# Transmitter_Schematic.net
KiCad netlist of a schematic drawn in EAGLE
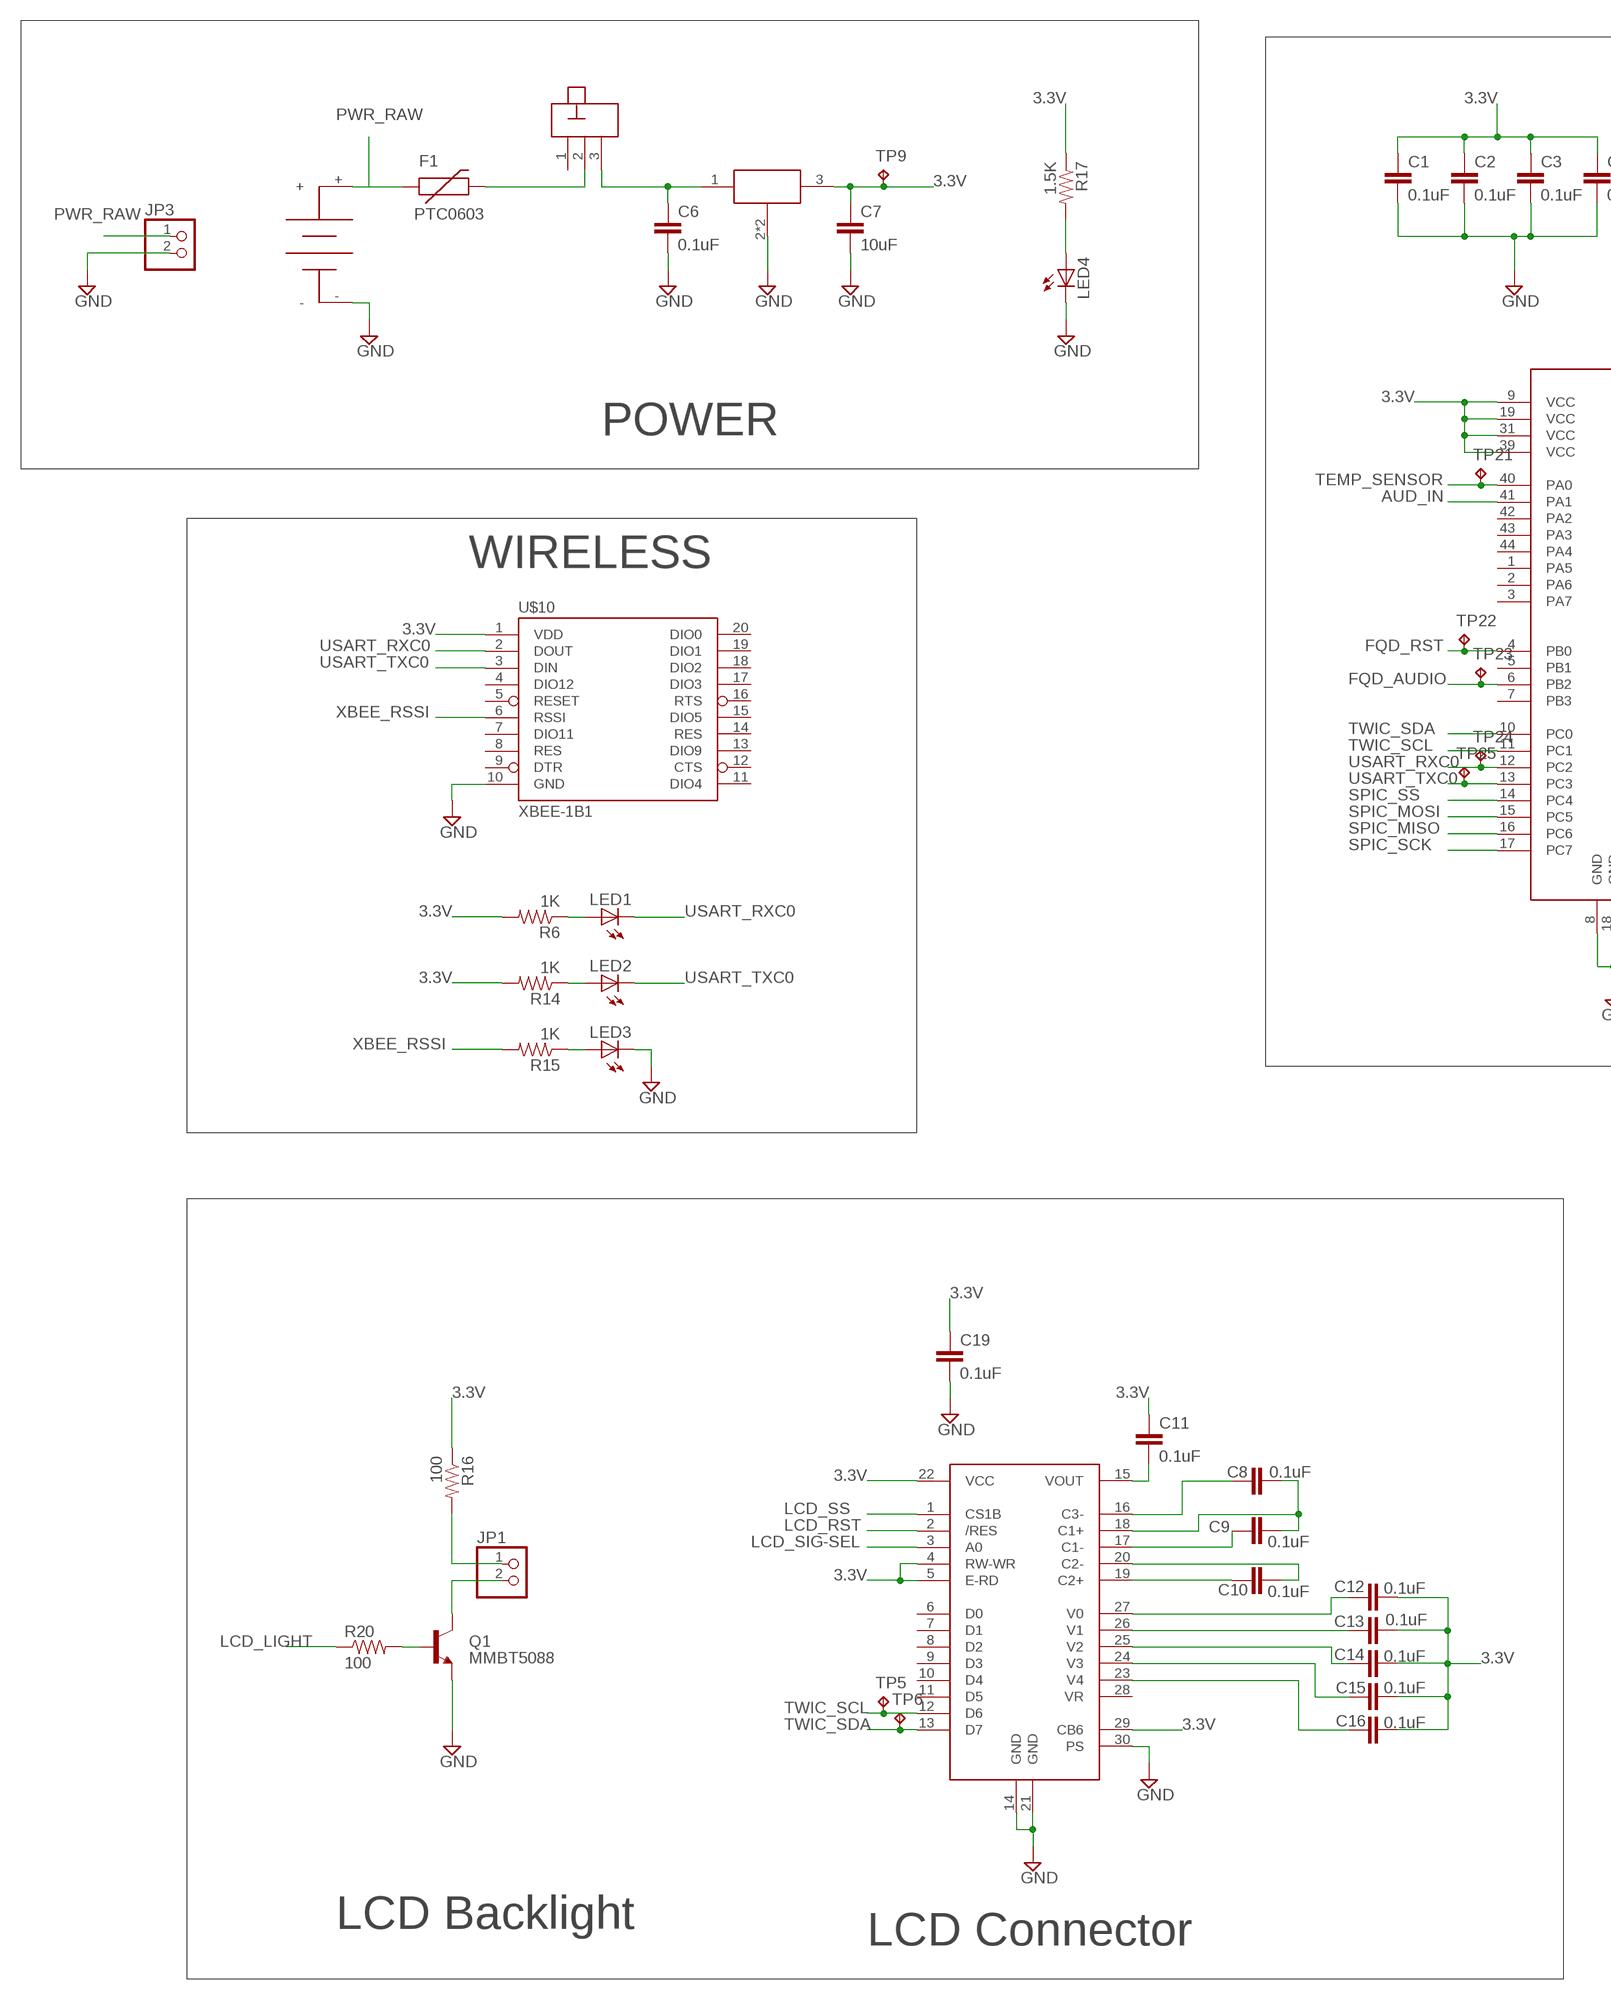
[diagram p0: schematic, sheet 1, part 1 of 2]
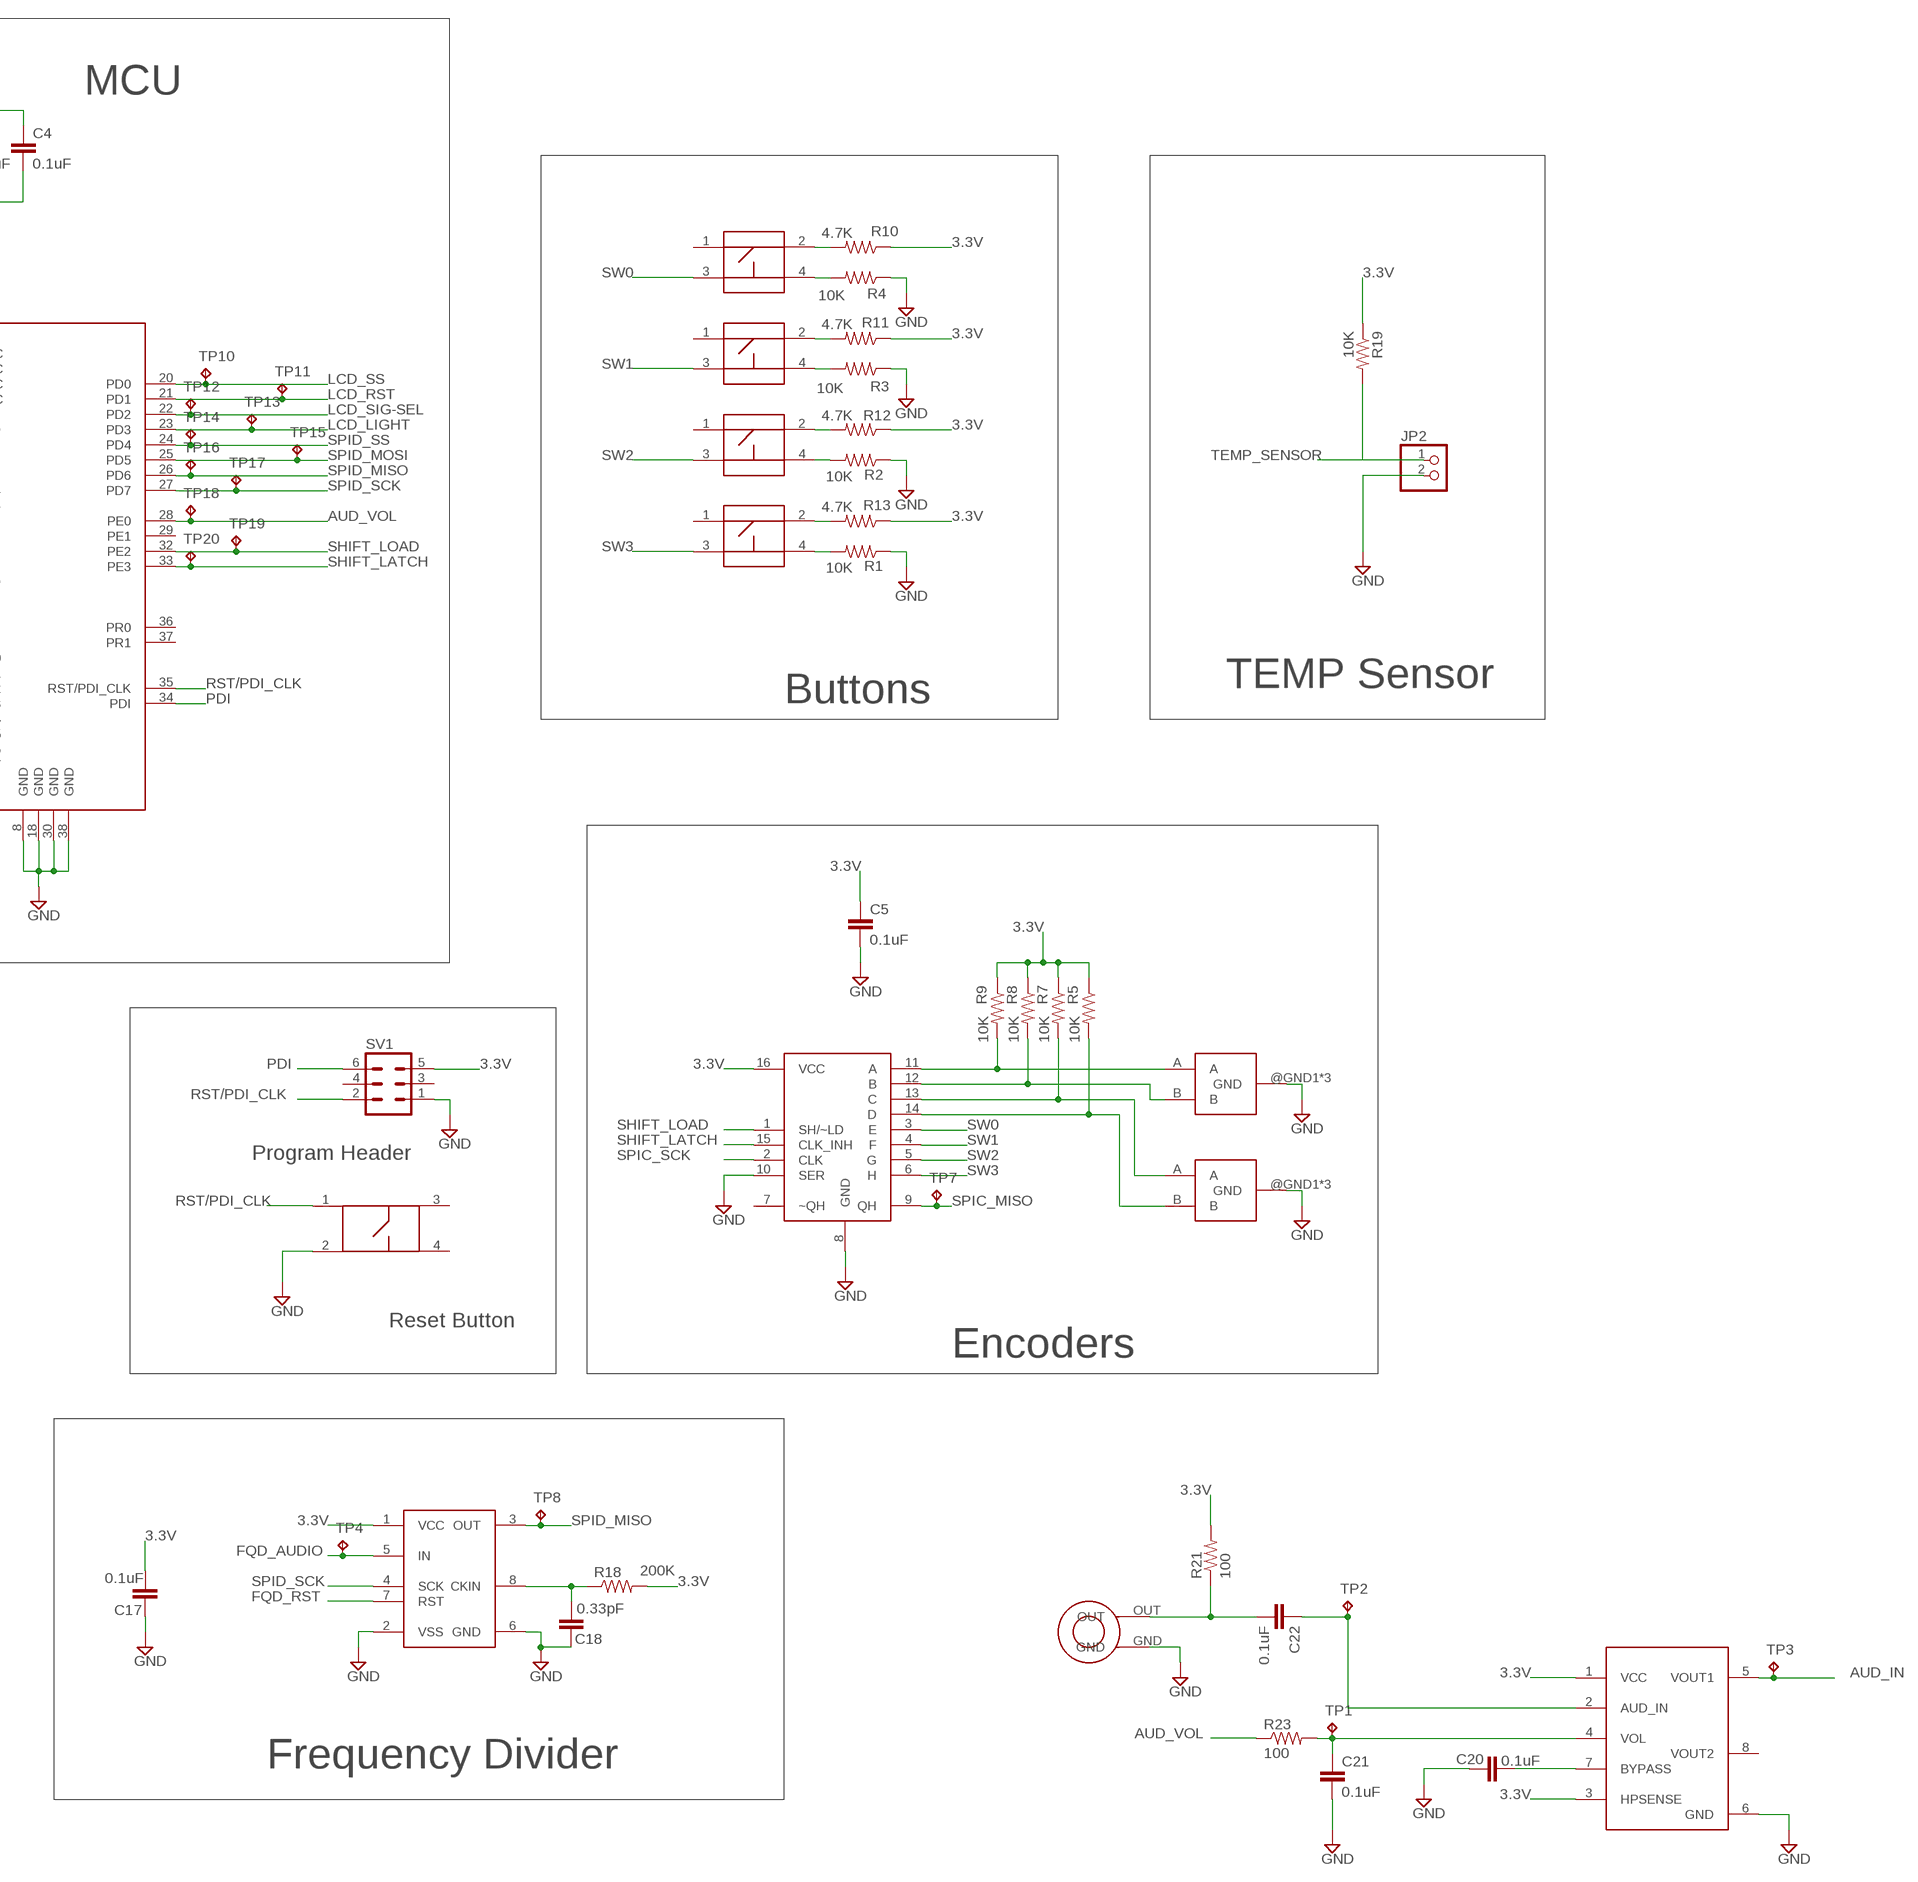
[diagram p1: schematic, sheet 1, part 2 of 2]

(export (version "E")
  (design (tool "Eeschema 10.0.6"))
  (components
    (comp (ref "C1")
      (value "0.1uF")
      (footprint "eagle-import:0603-CAP")
      (libsource (lib "eagle-import") (part "CAP0603-CAP"))
    )
    (comp (ref "C2")
      (value "0.1uF")
      (footprint "eagle-import:0603-CAP")
      (libsource (lib "eagle-import") (part "CAP0603-CAP"))
    )
    (comp (ref "C3")
      (value "0.1uF")
      (footprint "eagle-import:0603-CAP")
      (libsource (lib "eagle-import") (part "CAP0603-CAP"))
    )
    (comp (ref "C4")
      (value "0.1uF")
      (footprint "eagle-import:0603-CAP")
      (libsource (lib "eagle-import") (part "CAP0603-CAP"))
    )
    (comp (ref "C5")
      (value "0.1uF")
      (footprint "eagle-import:0603-CAP")
      (libsource (lib "eagle-import") (part "CAP0603-CAP"))
    )
    (comp (ref "C6")
      (value "0.1uF")
      (footprint "eagle-import:0603-CAP")
      (libsource (lib "eagle-import") (part "CAP0603-CAP"))
    )
    (comp (ref "C7")
      (value "10uF")
      (footprint "eagle-import:0603-CAP")
      (libsource (lib "eagle-import") (part "CAP0603-CAP"))
    )
    (comp (ref "C8")
      (value "0.1uF")
      (footprint "eagle-import:0603-CAP")
      (libsource (lib "eagle-import") (part "CAP0603-CAP"))
    )
    (comp (ref "C9")
      (value "0.1uF")
      (footprint "eagle-import:0603-CAP")
      (libsource (lib "eagle-import") (part "CAP0603-CAP"))
    )
    (comp (ref "C10")
      (value "0.1uF")
      (footprint "eagle-import:0603-CAP")
      (libsource (lib "eagle-import") (part "CAP0603-CAP"))
    )
    (comp (ref "C11")
      (value "0.1uF")
      (footprint "eagle-import:0603-CAP")
      (libsource (lib "eagle-import") (part "CAP0603-CAP"))
    )
    (comp (ref "C12")
      (value "0.1uF")
      (footprint "eagle-import:0603-CAP")
      (libsource (lib "eagle-import") (part "CAP0603-CAP"))
    )
    (comp (ref "C13")
      (value "0.1uF")
      (footprint "eagle-import:0603-CAP")
      (libsource (lib "eagle-import") (part "CAP0603-CAP"))
    )
    (comp (ref "C14")
      (value "0.1uF")
      (footprint "eagle-import:0603-CAP")
      (libsource (lib "eagle-import") (part "CAP0603-CAP"))
    )
    (comp (ref "C15")
      (value "0.1uF")
      (footprint "eagle-import:0603-CAP")
      (libsource (lib "eagle-import") (part "CAP0603-CAP"))
    )
    (comp (ref "C16")
      (value "0.1uF")
      (footprint "eagle-import:0603-CAP")
      (libsource (lib "eagle-import") (part "CAP0603-CAP"))
    )
    (comp (ref "C17")
      (value "0.1uF")
      (footprint "eagle-import:0603-CAP")
      (libsource (lib "eagle-import") (part "CAP0603-CAP"))
    )
    (comp (ref "C18")
      (value "0.33pF")
      (footprint "eagle-import:0603-CAP")
      (libsource (lib "eagle-import") (part "CAP0603-CAP"))
    )
    (comp (ref "C19")
      (value "0.1uF")
      (footprint "eagle-import:0603-CAP")
      (libsource (lib "eagle-import") (part "CAP0603-CAP"))
    )
    (comp (ref "C20")
      (value "0.1uF")
      (footprint "eagle-import:0603-CAP")
      (libsource (lib "eagle-import") (part "CAP0603-CAP"))
    )
    (comp (ref "C21")
      (value "0.1uF")
      (footprint "eagle-import:0603-CAP")
      (libsource (lib "eagle-import") (part "CAP0603-CAP"))
    )
    (comp (ref "C22")
      (value "0.1uF")
      (footprint "eagle-import:0603-CAP")
      (libsource (lib "eagle-import") (part "CAP0603-CAP"))
    )
    (comp (ref "F1")
      (value "PTC0603")
      (footprint "eagle-import:0603")
      (libsource (lib "eagle-import") (part "PTC0603"))
    )
    (comp (ref "JP1")
      (value "PINHD-1X2")
      (footprint "eagle-import:1X02")
      (libsource (lib "eagle-import") (part "PINHD-1X2"))
    )
    (comp (ref "JP2")
      (value "PINHD-1X2")
      (footprint "eagle-import:1X02")
      (libsource (lib "eagle-import") (part "PINHD-1X2"))
    )
    (comp (ref "JP3")
      (value "PINHD-1X2")
      (footprint "eagle-import:1X02")
      (libsource (lib "eagle-import") (part "PINHD-1X2"))
    )
    (comp (ref "LED1")
      (value "LED0603")
      (footprint "eagle-import:LED-0603")
      (libsource (lib "eagle-import") (part "LED0603"))
    )
    (comp (ref "LED2")
      (value "LED0603")
      (footprint "eagle-import:LED-0603")
      (libsource (lib "eagle-import") (part "LED0603"))
    )
    (comp (ref "LED3")
      (value "LED0603")
      (footprint "eagle-import:LED-0603")
      (libsource (lib "eagle-import") (part "LED0603"))
    )
    (comp (ref "LED4")
      (value "LED0603")
      (footprint "eagle-import:LED-0603")
      (libsource (lib "eagle-import") (part "LED0603"))
    )
    (comp (ref "Q1")
      (value "MMBT5088")
      (footprint "eagle-import:SOT23")
      (libsource (lib "eagle-import") (part "TRANSISTOR_NPNMMBT5088"))
    )
    (comp (ref "R1")
      (value "10K")
      (footprint "eagle-import:0603-RES")
      (libsource (lib "eagle-import") (part "RESISTOR0603"))
    )
    (comp (ref "R2")
      (value "10K")
      (footprint "eagle-import:0603-RES")
      (libsource (lib "eagle-import") (part "RESISTOR0603"))
    )
    (comp (ref "R3")
      (value "10K")
      (footprint "eagle-import:0603-RES")
      (libsource (lib "eagle-import") (part "RESISTOR0603"))
    )
    (comp (ref "R4")
      (value "10K")
      (footprint "eagle-import:0603-RES")
      (libsource (lib "eagle-import") (part "RESISTOR0603"))
    )
    (comp (ref "R5")
      (value "10K")
      (footprint "eagle-import:0603-RES")
      (libsource (lib "eagle-import") (part "RESISTOR0603"))
    )
    (comp (ref "R6")
      (value "1K")
      (footprint "eagle-import:0603-RES")
      (libsource (lib "eagle-import") (part "RESISTOR0603"))
    )
    (comp (ref "R7")
      (value "10K")
      (footprint "eagle-import:0603-RES")
      (libsource (lib "eagle-import") (part "RESISTOR0603"))
    )
    (comp (ref "R8")
      (value "10K")
      (footprint "eagle-import:0603-RES")
      (libsource (lib "eagle-import") (part "RESISTOR0603"))
    )
    (comp (ref "R9")
      (value "10K")
      (footprint "eagle-import:0603-RES")
      (libsource (lib "eagle-import") (part "RESISTOR0603"))
    )
    (comp (ref "R10")
      (value "4.7K")
      (footprint "eagle-import:0603-RES")
      (libsource (lib "eagle-import") (part "RESISTOR0603"))
    )
    (comp (ref "R11")
      (value "4.7K")
      (footprint "eagle-import:0603-RES")
      (libsource (lib "eagle-import") (part "RESISTOR0603"))
    )
    (comp (ref "R12")
      (value "4.7K")
      (footprint "eagle-import:0603-RES")
      (libsource (lib "eagle-import") (part "RESISTOR0603"))
    )
    (comp (ref "R13")
      (value "4.7K")
      (footprint "eagle-import:0603-RES")
      (libsource (lib "eagle-import") (part "RESISTOR0603"))
    )
    (comp (ref "R14")
      (value "1K")
      (footprint "eagle-import:0603-RES")
      (libsource (lib "eagle-import") (part "RESISTOR0603"))
    )
    (comp (ref "R15")
      (value "1K")
      (footprint "eagle-import:0603-RES")
      (libsource (lib "eagle-import") (part "RESISTOR0603"))
    )
    (comp (ref "R16")
      (value "100")
      (footprint "eagle-import:0603-RES")
      (libsource (lib "eagle-import") (part "RESISTOR0603"))
    )
    (comp (ref "R17")
      (value "1.5K")
      (footprint "eagle-import:0603-RES")
      (libsource (lib "eagle-import") (part "RESISTOR0603"))
    )
    (comp (ref "R18")
      (value "200K")
      (footprint "eagle-import:0603-RES")
      (libsource (lib "eagle-import") (part "RESISTOR0603"))
    )
    (comp (ref "R19")
      (value "10K")
      (footprint "eagle-import:0603-RES")
      (libsource (lib "eagle-import") (part "RESISTOR0603"))
    )
    (comp (ref "R20")
      (value "100")
      (footprint "eagle-import:0603-RES")
      (libsource (lib "eagle-import") (part "RESISTOR0603"))
    )
    (comp (ref "R21")
      (value "100")
      (footprint "eagle-import:0603-RES")
      (libsource (lib "eagle-import") (part "RESISTOR0603"))
    )
    (comp (ref "R23")
      (value "100")
      (footprint "eagle-import:0603-RES")
      (libsource (lib "eagle-import") (part "RESISTOR0603"))
    )
    (comp (ref "SV1")
      (value "MA03-2")
      (footprint "eagle-import:MA03-2")
      (libsource (lib "eagle-import") (part "MA03-2"))
    )
    (comp (ref "SW0")
      (value "SPARKFUN_TAC_BUTTONS")
      (footprint "eagle-import:SPARKFUN_TAC_BUTTONS")
      (libsource (lib "eagle-import") (part "SPARKFUN_TAC_BUTTONS"))
    )
    (comp (ref "SW1")
      (value "SPARKFUN_TAC_BUTTONS")
      (footprint "eagle-import:SPARKFUN_TAC_BUTTONS")
      (libsource (lib "eagle-import") (part "SPARKFUN_TAC_BUTTONS"))
    )
    (comp (ref "SW2")
      (value "SPARKFUN_TAC_BUTTONS")
      (footprint "eagle-import:SPARKFUN_TAC_BUTTONS")
      (libsource (lib "eagle-import") (part "SPARKFUN_TAC_BUTTONS"))
    )
    (comp (ref "SW3")
      (value "SPARKFUN_TAC_BUTTONS")
      (footprint "eagle-import:SPARKFUN_TAC_BUTTONS")
      (libsource (lib "eagle-import") (part "SPARKFUN_TAC_BUTTONS"))
    )
    (comp (ref "TP1")
      (value "TPPAD1-13")
      (footprint "eagle-import:P1-13")
      (libsource (lib "eagle-import") (part "TPPAD1-13"))
    )
    (comp (ref "TP2")
      (value "TPPAD1-13")
      (footprint "eagle-import:P1-13")
      (libsource (lib "eagle-import") (part "TPPAD1-13"))
    )
    (comp (ref "TP3")
      (value "TPPAD1-13")
      (footprint "eagle-import:P1-13")
      (libsource (lib "eagle-import") (part "TPPAD1-13"))
    )
    (comp (ref "TP4")
      (value "TPPAD1-13")
      (footprint "eagle-import:P1-13")
      (libsource (lib "eagle-import") (part "TPPAD1-13"))
    )
    (comp (ref "TP5")
      (value "TPPAD1-13")
      (footprint "eagle-import:P1-13")
      (libsource (lib "eagle-import") (part "TPPAD1-13"))
    )
    (comp (ref "TP6")
      (value "TPPAD1-13")
      (footprint "eagle-import:P1-13")
      (libsource (lib "eagle-import") (part "TPPAD1-13"))
    )
    (comp (ref "TP7")
      (value "TPPAD1-13")
      (footprint "eagle-import:P1-13")
      (libsource (lib "eagle-import") (part "TPPAD1-13"))
    )
    (comp (ref "TP8")
      (value "TPPAD1-13")
      (footprint "eagle-import:P1-13")
      (libsource (lib "eagle-import") (part "TPPAD1-13"))
    )
    (comp (ref "TP9")
      (value "TPPAD1-13")
      (footprint "eagle-import:P1-13")
      (libsource (lib "eagle-import") (part "TPPAD1-13"))
    )
    (comp (ref "TP10")
      (value "TPPAD1-13")
      (footprint "eagle-import:P1-13")
      (libsource (lib "eagle-import") (part "TPPAD1-13"))
    )
    (comp (ref "TP11")
      (value "TPPAD1-13")
      (footprint "eagle-import:P1-13")
      (libsource (lib "eagle-import") (part "TPPAD1-13"))
    )
    (comp (ref "TP12")
      (value "TPPAD1-13")
      (footprint "eagle-import:P1-13")
      (libsource (lib "eagle-import") (part "TPPAD1-13"))
    )
    (comp (ref "TP13")
      (value "TPPAD1-13")
      (footprint "eagle-import:P1-13")
      (libsource (lib "eagle-import") (part "TPPAD1-13"))
    )
    (comp (ref "TP14")
      (value "TPPAD1-13")
      (footprint "eagle-import:P1-13")
      (libsource (lib "eagle-import") (part "TPPAD1-13"))
    )
    (comp (ref "TP15")
      (value "TPPAD1-13")
      (footprint "eagle-import:P1-13")
      (libsource (lib "eagle-import") (part "TPPAD1-13"))
    )
    (comp (ref "TP16")
      (value "TPPAD1-13")
      (footprint "eagle-import:P1-13")
      (libsource (lib "eagle-import") (part "TPPAD1-13"))
    )
    (comp (ref "TP17")
      (value "TPPAD1-13")
      (footprint "eagle-import:P1-13")
      (libsource (lib "eagle-import") (part "TPPAD1-13"))
    )
    (comp (ref "TP18")
      (value "TPPAD1-13")
      (footprint "eagle-import:P1-13")
      (libsource (lib "eagle-import") (part "TPPAD1-13"))
    )
    (comp (ref "TP19")
      (value "TPPAD1-13")
      (footprint "eagle-import:P1-13")
      (libsource (lib "eagle-import") (part "TPPAD1-13"))
    )
    (comp (ref "TP20")
      (value "TPPAD1-13")
      (footprint "eagle-import:P1-13")
      (libsource (lib "eagle-import") (part "TPPAD1-13"))
    )
    (comp (ref "TP21")
      (value "TPPAD1-13")
      (footprint "eagle-import:P1-13")
      (libsource (lib "eagle-import") (part "TPPAD1-13"))
    )
    (comp (ref "TP22")
      (value "TPPAD1-13")
      (footprint "eagle-import:P1-13")
      (libsource (lib "eagle-import") (part "TPPAD1-13"))
    )
    (comp (ref "TP23")
      (value "TPPAD1-13")
      (footprint "eagle-import:P1-13")
      (libsource (lib "eagle-import") (part "TPPAD1-13"))
    )
    (comp (ref "TP24")
      (value "TPPAD1-13")
      (footprint "eagle-import:P1-13")
      (libsource (lib "eagle-import") (part "TPPAD1-13"))
    )
    (comp (ref "TP25")
      (value "TPPAD1-13")
      (footprint "eagle-import:P1-13")
      (libsource (lib "eagle-import") (part "TPPAD1-13"))
    )
    (comp (ref "U$1")
      (value "ATXMEGA32A4UTQFP44")
      (footprint "eagle-import:QFP80P1200X1200X120-44N")
      (libsource (lib "eagle-import") (part "ATXMEGA32A4UTQFP44"))
    )
    (comp (ref "U$6")
      (value "8B_SHIFT_REG")
      (footprint "eagle-import:TSSOP16")
      (libsource (lib "eagle-import") (part "8B_SHIFT_REG"))
    )
    (comp (ref "U$7")
      (value "MICRO_TAC_BUTTONS")
      (footprint "eagle-import:MICRO_TAC_BUTTONS")
      (libsource (lib "eagle-import") (part "MICRO_TAC_BUTTONS"))
    )
    (comp (ref "U$8")
      (value "ENCODER")
      (footprint "eagle-import:EVE_GE1F2012B")
      (libsource (lib "eagle-import") (part "ENCODER"))
    )
    (comp (ref "U$9")
      (value "ENCODER")
      (footprint "eagle-import:EVE_GE1F2012B")
      (libsource (lib "eagle-import") (part "ENCODER"))
    )
    (comp (ref "U$10")
      (value "XBEE-1B1")
      (footprint "eagle-import:XBEE-1")
      (libsource (lib "eagle-import") (part "XBEE-1B1"))
    )
    (comp (ref "U$11")
      (value "LCD_CONNECTOR")
      (footprint "eagle-import:LCD_CONNECTOR")
      (libsource (lib "eagle-import") (part "LCD_CONNECTOR"))
    )
    (comp (ref "U$12")
      (value "3.3V_REG_LDO")
      (footprint "eagle-import:SOT223")
      (libsource (lib "eagle-import") (part "3.3V_REG_LDO"))
    )
    (comp (ref "U$13")
      (value "3XAA_BATT_HOLDER")
      (footprint "eagle-import:3XAA_BATT_HOLDER")
      (libsource (lib "eagle-import") (part "3XAA_BATT_HOLDER"))
    )
    (comp (ref "U$14")
      (value "SWITCH_SLIDE")
      (footprint "eagle-import:SWITCH_SLIDE")
      (libsource (lib "eagle-import") (part "SWITCH_SLIDE"))
    )
    (comp (ref "U$15")
      (value "FREQUENCY_DIVIDER")
      (footprint "eagle-import:DIP08")
      (libsource (lib "eagle-import") (part "FREQUENCY_DIVIDER"))
    )
    (comp (ref "U$16")
      (value "LM4875")
      (footprint "eagle-import:SOIC8")
      (libsource (lib "eagle-import") (part "LM4875"))
    )
    (comp (ref "U$17")
      (value "MICROPHONE")
      (footprint "eagle-import:CMA-4544PF")
      (libsource (lib "eagle-import") (part "MICROPHONE"))
    )
  )
  (nets
    (net (code "1") (name "/3.3V") (class "Default")
      (node (ref "C1") (pin "1") (pinfunction "1_1") (pintype "passive"))
      (node (ref "C11") (pin "1") (pinfunction "1_1") (pintype "passive"))
      (node (ref "C12") (pin "2") (pinfunction "2_2") (pintype "passive"))
      (node (ref "C13") (pin "2") (pinfunction "2_2") (pintype "passive"))
      (node (ref "C14") (pin "2") (pinfunction "2_2") (pintype "passive"))
      (node (ref "C15") (pin "2") (pinfunction "2_2") (pintype "passive"))
      (node (ref "C16") (pin "2") (pinfunction "2_2") (pintype "passive"))
      (node (ref "C17") (pin "2") (pinfunction "2_2") (pintype "passive"))
      (node (ref "C19") (pin "1") (pinfunction "1_1") (pintype "passive"))
      (node (ref "C2") (pin "1") (pinfunction "1_1") (pintype "passive"))
      (node (ref "C3") (pin "1") (pinfunction "1_1") (pintype "passive"))
      (node (ref "C4") (pin "1") (pinfunction "1_1") (pintype "passive"))
      (node (ref "C5") (pin "1") (pinfunction "1_1") (pintype "passive"))
      (node (ref "C7") (pin "1") (pinfunction "1_1") (pintype "passive"))
      (node (ref "R10") (pin "1") (pinfunction "1_1") (pintype "passive"))
      (node (ref "R11") (pin "1") (pinfunction "1_1") (pintype "passive"))
      (node (ref "R12") (pin "1") (pinfunction "1_1") (pintype "passive"))
      (node (ref "R13") (pin "1") (pinfunction "1_1") (pintype "passive"))
      (node (ref "R14") (pin "2") (pinfunction "2_2") (pintype "passive"))
      (node (ref "R16") (pin "1") (pinfunction "1_1") (pintype "passive"))
      (node (ref "R17") (pin "1") (pinfunction "1_1") (pintype "passive"))
      (node (ref "R18") (pin "2") (pinfunction "2_2") (pintype "passive"))
      (node (ref "R19") (pin "1") (pinfunction "1_1") (pintype "passive"))
      (node (ref "R21") (pin "2") (pinfunction "2_2") (pintype "passive"))
      (node (ref "R5") (pin "1") (pinfunction "1_1") (pintype "passive"))
      (node (ref "R6") (pin "2") (pinfunction "2_2") (pintype "passive"))
      (node (ref "R7") (pin "1") (pinfunction "1_1") (pintype "passive"))
      (node (ref "R8") (pin "1") (pinfunction "1_1") (pintype "passive"))
      (node (ref "R9") (pin "1") (pinfunction "1_1") (pintype "passive"))
      (node (ref "SV1") (pin "5") (pinfunction "5_5") (pintype "passive"))
      (node (ref "TP9") (pin "TP") (pinfunction "TP_TP") (pintype "input"))
      (node (ref "U$1") (pin "19") (pinfunction "VCC_19") (pintype "bidirectional"))
      (node (ref "U$1") (pin "31") (pinfunction "VCC_31") (pintype "bidirectional"))
      (node (ref "U$1") (pin "39") (pinfunction "VCC_39") (pintype "bidirectional"))
      (node (ref "U$1") (pin "9") (pinfunction "VCC_9") (pintype "bidirectional"))
      (node (ref "U$10") (pin "1") (pinfunction "VDD_1") (pintype "power_in"))
      (node (ref "U$11") (pin "22") (pinfunction "VCC_22") (pintype "bidirectional"))
      (node (ref "U$11") (pin "29") (pinfunction "CB6_29") (pintype "bidirectional"))
      (node (ref "U$11") (pin "4") (pinfunction "RW-WR_4") (pintype "bidirectional"))
      (node (ref "U$11") (pin "5") (pinfunction "E-RD_5") (pintype "bidirectional"))
      (node (ref "U$12") (pin "3") (pintype "bidirectional"))
      (node (ref "U$15") (pin "1") (pinfunction "VCC_1") (pintype "bidirectional"))
      (node (ref "U$16") (pin "1") (pinfunction "VCC_1") (pintype "bidirectional"))
      (node (ref "U$16") (pin "3") (pinfunction "HPSENSE_3") (pintype "bidirectional"))
      (node (ref "U$6") (pin "16") (pinfunction "VCC_16") (pintype "bidirectional"))
    )
    (net (code "2") (name "/AUD_IN") (class "Default")
      (node (ref "TP3") (pin "TP") (pinfunction "TP_TP") (pintype "input"))
      (node (ref "U$1") (pin "41") (pinfunction "PA1_41") (pintype "bidirectional"))
      (node (ref "U$16") (pin "5") (pinfunction "VOUT1_5") (pintype "bidirectional"))
    )
    (net (code "3") (name "/AUD_VOL") (class "Default")
      (node (ref "R23") (pin "1") (pinfunction "1_1") (pintype "passive"))
      (node (ref "TP18") (pin "TP") (pinfunction "TP_TP") (pintype "input"))
      (node (ref "U$1") (pin "28") (pinfunction "PE0_28") (pintype "bidirectional"))
    )
    (net (code "4") (name "/FQD_AUDIO") (class "Default")
      (node (ref "TP23") (pin "TP") (pinfunction "TP_TP") (pintype "input"))
      (node (ref "TP4") (pin "TP") (pinfunction "TP_TP") (pintype "input"))
      (node (ref "U$1") (pin "6") (pinfunction "PB2_6") (pintype "bidirectional"))
      (node (ref "U$15") (pin "5") (pinfunction "IN_5") (pintype "bidirectional"))
    )
    (net (code "5") (name "/FQD_RST") (class "Default")
      (node (ref "TP22") (pin "TP") (pinfunction "TP_TP") (pintype "input"))
      (node (ref "U$1") (pin "4") (pinfunction "PB0_4") (pintype "bidirectional"))
      (node (ref "U$15") (pin "7") (pinfunction "RST_7") (pintype "bidirectional"))
    )
    (net (code "6") (name "/LCD_LIGHT") (class "Default")
      (node (ref "R20") (pin "1") (pinfunction "1_1") (pintype "passive"))
      (node (ref "TP13") (pin "TP") (pinfunction "TP_TP") (pintype "input"))
      (node (ref "U$1") (pin "23") (pinfunction "PD3_23") (pintype "bidirectional"))
    )
    (net (code "7") (name "/LCD_RST") (class "Default")
      (node (ref "TP11") (pin "TP") (pinfunction "TP_TP") (pintype "input"))
      (node (ref "U$1") (pin "21") (pinfunction "PD1_21") (pintype "bidirectional"))
      (node (ref "U$11") (pin "2") (pinfunction "/RES_2") (pintype "bidirectional"))
    )
    (net (code "8") (name "/LCD_SIG-SEL") (class "Default")
      (node (ref "TP12") (pin "TP") (pinfunction "TP_TP") (pintype "input"))
      (node (ref "U$1") (pin "22") (pinfunction "PD2_22") (pintype "bidirectional"))
      (node (ref "U$11") (pin "3") (pinfunction "A0_3") (pintype "bidirectional"))
    )
    (net (code "9") (name "/LCD_SS") (class "Default")
      (node (ref "TP10") (pin "TP") (pinfunction "TP_TP") (pintype "input"))
      (node (ref "U$1") (pin "20") (pinfunction "PD0_20") (pintype "bidirectional"))
      (node (ref "U$11") (pin "1") (pinfunction "CS1B_1") (pintype "bidirectional"))
    )
    (net (code "10") (name "/PDI") (class "Default")
      (node (ref "SV1") (pin "6") (pinfunction "6_6") (pintype "passive"))
      (node (ref "U$1") (pin "34") (pinfunction "PDI_34") (pintype "bidirectional"))
    )
    (net (code "11") (name "/PWR_RAW") (class "Default")
      (node (ref "F1") (pin "1") (pinfunction "1_1") (pintype "bidirectional"))
      (node (ref "JP3") (pin "1") (pinfunction "1_1") (pintype "passive"))
      (node (ref "U$13") (pin "+") (pinfunction "+_+") (pintype "bidirectional"))
    )
    (net (code "12") (name "/RST{slash}PDI_CLK") (class "Default")
      (node (ref "SV1") (pin "2") (pinfunction "2_2") (pintype "passive"))
      (node (ref "U$1") (pin "35") (pinfunction "RST/PDI_CLK_35") (pintype "bidirectional"))
      (node (ref "U$7") (pin "1") (pintype "bidirectional"))
    )
    (net (code "13") (name "/SHIFT_LATCH") (class "Default")
      (node (ref "TP20") (pin "TP") (pinfunction "TP_TP") (pintype "input"))
      (node (ref "U$1") (pin "33") (pinfunction "PE3_33") (pintype "bidirectional"))
      (node (ref "U$6") (pin "15") (pinfunction "CLK_INH_15") (pintype "bidirectional"))
    )
    (net (code "14") (name "/SHIFT_LOAD") (class "Default")
      (node (ref "TP19") (pin "TP") (pinfunction "TP_TP") (pintype "input"))
      (node (ref "U$1") (pin "32") (pinfunction "PE2_32") (pintype "bidirectional"))
      (node (ref "U$6") (pin "1") (pinfunction "SH/~{LD}_1") (pintype "bidirectional"))
    )
    (net (code "15") (name "/SPIC_MISO") (class "Default")
      (node (ref "TP7") (pin "TP") (pinfunction "TP_TP") (pintype "input"))
      (node (ref "U$1") (pin "16") (pinfunction "PC6_16") (pintype "bidirectional"))
      (node (ref "U$6") (pin "9") (pinfunction "QH_9") (pintype "bidirectional"))
    )
    (net (code "16") (name "/SPIC_MOSI") (class "Default")
      (node (ref "U$1") (pin "15") (pinfunction "PC5_15") (pintype "bidirectional"))
    )
    (net (code "17") (name "/SPIC_SCK") (class "Default")
      (node (ref "U$1") (pin "17") (pinfunction "PC7_17") (pintype "bidirectional"))
      (node (ref "U$6") (pin "2") (pinfunction "CLK_2") (pintype "bidirectional"))
    )
    (net (code "18") (name "/SPIC_SS") (class "Default")
      (node (ref "U$1") (pin "14") (pinfunction "PC4_14") (pintype "bidirectional"))
    )
    (net (code "19") (name "/SPID_MISO") (class "Default")
      (node (ref "TP16") (pin "TP") (pinfunction "TP_TP") (pintype "input"))
      (node (ref "TP8") (pin "TP") (pinfunction "TP_TP") (pintype "input"))
      (node (ref "U$1") (pin "26") (pinfunction "PD6_26") (pintype "bidirectional"))
      (node (ref "U$15") (pin "3") (pinfunction "OUT_3") (pintype "bidirectional"))
    )
    (net (code "20") (name "/SPID_MOSI") (class "Default")
      (node (ref "TP15") (pin "TP") (pinfunction "TP_TP") (pintype "input"))
      (node (ref "U$1") (pin "25") (pinfunction "PD5_25") (pintype "bidirectional"))
    )
    (net (code "21") (name "/SPID_SCK") (class "Default")
      (node (ref "TP17") (pin "TP") (pinfunction "TP_TP") (pintype "input"))
      (node (ref "U$1") (pin "27") (pinfunction "PD7_27") (pintype "bidirectional"))
      (node (ref "U$15") (pin "4") (pinfunction "SCK_4") (pintype "bidirectional"))
    )
    (net (code "22") (name "/SPID_SS") (class "Default")
      (node (ref "TP14") (pin "TP") (pinfunction "TP_TP") (pintype "input"))
      (node (ref "U$1") (pin "24") (pinfunction "PD4_24") (pintype "bidirectional"))
    )
    (net (code "23") (name "/SW0") (class "Default")
      (node (ref "SW0") (pin "3") (pintype "bidirectional"))
      (node (ref "U$6") (pin "3") (pinfunction "E_3") (pintype "bidirectional"))
    )
    (net (code "24") (name "/SW1") (class "Default")
      (node (ref "SW1") (pin "3") (pintype "bidirectional"))
      (node (ref "U$6") (pin "4") (pinfunction "F_4") (pintype "bidirectional"))
    )
    (net (code "25") (name "/SW2") (class "Default")
      (node (ref "SW2") (pin "3") (pintype "bidirectional"))
      (node (ref "U$6") (pin "5") (pinfunction "G_5") (pintype "bidirectional"))
    )
    (net (code "26") (name "/SW3") (class "Default")
      (node (ref "SW3") (pin "3") (pintype "bidirectional"))
      (node (ref "U$6") (pin "6") (pinfunction "H_6") (pintype "bidirectional"))
    )
    (net (code "27") (name "/TEMP_SENSOR") (class "Default")
      (node (ref "JP2") (pin "1") (pinfunction "1_1") (pintype "passive"))
      (node (ref "R19") (pin "2") (pinfunction "2_2") (pintype "passive"))
      (node (ref "TP21") (pin "TP") (pinfunction "TP_TP") (pintype "input"))
      (node (ref "U$1") (pin "40") (pinfunction "PA0_40") (pintype "bidirectional"))
    )
    (net (code "28") (name "/TWIC_SCL") (class "Default")
      (node (ref "TP5") (pin "TP") (pinfunction "TP_TP") (pintype "input"))
      (node (ref "U$1") (pin "11") (pinfunction "PC1_11") (pintype "bidirectional"))
      (node (ref "U$11") (pin "12") (pinfunction "D6_12") (pintype "bidirectional"))
    )
    (net (code "29") (name "/TWIC_SDA") (class "Default")
      (node (ref "TP6") (pin "TP") (pinfunction "TP_TP") (pintype "input"))
      (node (ref "U$1") (pin "10") (pinfunction "PC0_10") (pintype "bidirectional"))
      (node (ref "U$11") (pin "13") (pinfunction "D7_13") (pintype "bidirectional"))
    )
    (net (code "30") (name "/USART_RXC0") (class "Default")
      (node (ref "LED1") (pin "C") (pinfunction "C_C") (pintype "passive"))
      (node (ref "TP24") (pin "TP") (pinfunction "TP_TP") (pintype "input"))
      (node (ref "U$1") (pin "12") (pinfunction "PC2_12") (pintype "bidirectional"))
      (node (ref "U$10") (pin "2") (pinfunction "DOUT_2") (pintype "output"))
    )
    (net (code "31") (name "/USART_TXC0") (class "Default")
      (node (ref "LED2") (pin "C") (pinfunction "C_C") (pintype "passive"))
      (node (ref "TP25") (pin "TP") (pinfunction "TP_TP") (pintype "input"))
      (node (ref "U$1") (pin "13") (pinfunction "PC3_13") (pintype "bidirectional"))
      (node (ref "U$10") (pin "3") (pinfunction "DIN_3") (pintype "input"))
    )
    (net (code "32") (name "/XBEE_RSSI") (class "Default")
      (node (ref "R15") (pin "2") (pinfunction "2_2") (pintype "passive"))
      (node (ref "U$10") (pin "6") (pinfunction "RSSI_6") (pintype "bidirectional"))
    )
    (net (code "33") (name "GND") (class "Default")
      (node (ref "C1") (pin "2") (pinfunction "2_2") (pintype "passive"))
      (node (ref "C17") (pin "1") (pinfunction "1_1") (pintype "passive"))
      (node (ref "C18") (pin "1") (pinfunction "1_1") (pintype "passive"))
      (node (ref "C19") (pin "2") (pinfunction "2_2") (pintype "passive"))
      (node (ref "C2") (pin "2") (pinfunction "2_2") (pintype "passive"))
      (node (ref "C20") (pin "1") (pinfunction "1_1") (pintype "passive"))
      (node (ref "C21") (pin "2") (pinfunction "2_2") (pintype "passive"))
      (node (ref "C3") (pin "2") (pinfunction "2_2") (pintype "passive"))
      (node (ref "C4") (pin "2") (pinfunction "2_2") (pintype "passive"))
      (node (ref "C5") (pin "2") (pinfunction "2_2") (pintype "passive"))
      (node (ref "C6") (pin "2") (pinfunction "2_2") (pintype "passive"))
      (node (ref "C7") (pin "2") (pinfunction "2_2") (pintype "passive"))
      (node (ref "JP2") (pin "2") (pinfunction "2_2") (pintype "passive"))
      (node (ref "JP3") (pin "2") (pinfunction "2_2") (pintype "passive"))
      (node (ref "LED3") (pin "C") (pinfunction "C_C") (pintype "passive"))
      (node (ref "LED4") (pin "C") (pinfunction "C_C") (pintype "passive"))
      (node (ref "Q1") (pin "2") (pinfunction "E_2") (pintype "passive"))
      (node (ref "R1") (pin "1") (pinfunction "1_1") (pintype "passive"))
      (node (ref "R2") (pin "1") (pinfunction "1_1") (pintype "passive"))
      (node (ref "R3") (pin "1") (pinfunction "1_1") (pintype "passive"))
      (node (ref "R4") (pin "1") (pinfunction "1_1") (pintype "passive"))
      (node (ref "SV1") (pin "1") (pinfunction "1_1") (pintype "passive"))
      (node (ref "U$1") (pin "18") (pinfunction "GND_18") (pintype "bidirectional"))
      (node (ref "U$1") (pin "30") (pinfunction "GND_30") (pintype "bidirectional"))
      (node (ref "U$1") (pin "38") (pinfunction "GND_38") (pintype "bidirectional"))
      (node (ref "U$1") (pin "8") (pinfunction "GND_8") (pintype "bidirectional"))
      (node (ref "U$10") (pin "10") (pinfunction "GND_10") (pintype "power_in"))
      (node (ref "U$11") (pin "14") (pinfunction "GND_14") (pintype "bidirectional"))
      (node (ref "U$11") (pin "21") (pinfunction "GND_21") (pintype "bidirectional"))
      (node (ref "U$11") (pin "30") (pinfunction "PS_30") (pintype "bidirectional"))
      (node (ref "U$12") (pin "2") (pintype "bidirectional"))
      (node (ref "U$12") (pin "4") (pintype "bidirectional"))
      (node (ref "U$13") (pin "-") (pinfunction "-_-") (pintype "bidirectional"))
      (node (ref "U$15") (pin "2") (pinfunction "VSS_2") (pintype "bidirectional"))
      (node (ref "U$15") (pin "6") (pinfunction "GND_6") (pintype "bidirectional"))
      (node (ref "U$16") (pin "6") (pinfunction "GND_6") (pintype "bidirectional"))
      (node (ref "U$17") (pin "GND") (pinfunction "GND_GND") (pintype "bidirectional"))
      (node (ref "U$6") (pin "10") (pinfunction "SER_10") (pintype "bidirectional"))
      (node (ref "U$6") (pin "8") (pinfunction "GND_8") (pintype "bidirectional"))
      (node (ref "U$7") (pin "2") (pintype "bidirectional"))
      (node (ref "U$8") (pin "@GND1") (pinfunction "GND_@GND1") (pintype "bidirectional"))
      (node (ref "U$8") (pin "@GND2") (pinfunction "GND_@GND2") (pintype "bidirectional"))
      (node (ref "U$8") (pin "GND") (pinfunction "GND_GND") (pintype "bidirectional"))
      (node (ref "U$9") (pin "@GND1") (pinfunction "GND_@GND1") (pintype "bidirectional"))
      (node (ref "U$9") (pin "@GND2") (pinfunction "GND_@GND2") (pintype "bidirectional"))
      (node (ref "U$9") (pin "GND") (pinfunction "GND_GND") (pintype "bidirectional"))
    )
    (net (code "34") (name "Net-(C6-Pad1)") (class "Default")
      (node (ref "C6") (pin "1") (pinfunction "1_1") (pintype "passive"))
      (node (ref "U$12") (pin "1") (pintype "bidirectional"))
      (node (ref "U$14") (pin "3") (pintype "bidirectional"))
    )
    (net (code "35") (name "Net-(C22-Pad2)") (class "Default")
      (node (ref "C22") (pin "2") (pinfunction "2_2") (pintype "passive"))
      (node (ref "R21") (pin "1") (pinfunction "1_1") (pintype "passive"))
      (node (ref "U$17") (pin "OUT") (pinfunction "OUT_OUT") (pintype "bidirectional"))
    )
    (net (code "36") (name "Net-(F1-Pad2)") (class "Default")
      (node (ref "F1") (pin "2") (pinfunction "2_2") (pintype "bidirectional"))
      (node (ref "U$14") (pin "2") (pintype "bidirectional"))
    )
    (net (code "37") (name "Net-(JP1-Pad1)") (class "Default")
      (node (ref "JP1") (pin "1") (pinfunction "1_1") (pintype "passive"))
      (node (ref "R16") (pin "2") (pinfunction "2_2") (pintype "passive"))
    )
    (net (code "38") (name "Net-(LED1-PadA)") (class "Default")
      (node (ref "LED1") (pin "A") (pinfunction "A_A") (pintype "passive"))
      (node (ref "R6") (pin "1") (pinfunction "1_1") (pintype "passive"))
    )
    (net (code "39") (name "Net-(LED2-PadA)") (class "Default")
      (node (ref "LED2") (pin "A") (pinfunction "A_A") (pintype "passive"))
      (node (ref "R14") (pin "1") (pinfunction "1_1") (pintype "passive"))
    )
    (net (code "40") (name "Net-(LED3-PadA)") (class "Default")
      (node (ref "LED3") (pin "A") (pinfunction "A_A") (pintype "passive"))
      (node (ref "R15") (pin "1") (pinfunction "1_1") (pintype "passive"))
    )
    (net (code "41") (name "Net-(LED4-PadA)") (class "Default")
      (node (ref "LED4") (pin "A") (pinfunction "A_A") (pintype "passive"))
      (node (ref "R17") (pin "2") (pinfunction "2_2") (pintype "passive"))
    )
    (net (code "42") (name "Net-(Q1-B)") (class "Default")
      (node (ref "Q1") (pin "1") (pinfunction "B_1") (pintype "passive"))
      (node (ref "R20") (pin "2") (pinfunction "2_2") (pintype "passive"))
    )
    (net (code "43") (name "Net-(Q1-C)") (class "Default")
      (node (ref "JP1") (pin "2") (pinfunction "2_2") (pintype "passive"))
      (node (ref "Q1") (pin "3") (pinfunction "C_3") (pintype "passive"))
    )
    (net (code "44") (name "Net-(R1-Pad2)") (class "Default")
      (node (ref "R1") (pin "2") (pinfunction "2_2") (pintype "passive"))
      (node (ref "SW3") (pin "4") (pintype "bidirectional"))
    )
    (net (code "45") (name "Net-(R2-Pad2)") (class "Default")
      (node (ref "R2") (pin "2") (pinfunction "2_2") (pintype "passive"))
      (node (ref "SW2") (pin "4") (pintype "bidirectional"))
    )
    (net (code "46") (name "Net-(R3-Pad2)") (class "Default")
      (node (ref "R3") (pin "2") (pinfunction "2_2") (pintype "passive"))
      (node (ref "SW1") (pin "4") (pintype "bidirectional"))
    )
    (net (code "47") (name "Net-(R4-Pad2)") (class "Default")
      (node (ref "R4") (pin "2") (pinfunction "2_2") (pintype "passive"))
      (node (ref "SW0") (pin "4") (pintype "bidirectional"))
    )
    (net (code "48") (name "Net-(R10-Pad2)") (class "Default")
      (node (ref "R10") (pin "2") (pinfunction "2_2") (pintype "passive"))
      (node (ref "SW0") (pin "2") (pintype "bidirectional"))
    )
    (net (code "49") (name "Net-(R11-Pad2)") (class "Default")
      (node (ref "R11") (pin "2") (pinfunction "2_2") (pintype "passive"))
      (node (ref "SW1") (pin "2") (pintype "bidirectional"))
    )
    (net (code "50") (name "Net-(R12-Pad2)") (class "Default")
      (node (ref "R12") (pin "2") (pinfunction "2_2") (pintype "passive"))
      (node (ref "SW2") (pin "2") (pintype "bidirectional"))
    )
    (net (code "51") (name "Net-(R13-Pad2)") (class "Default")
      (node (ref "R13") (pin "2") (pinfunction "2_2") (pintype "passive"))
      (node (ref "SW3") (pin "2") (pintype "bidirectional"))
    )
    (net (code "52") (name "Net-(U$6-A)") (class "Default")
      (node (ref "R9") (pin "2") (pinfunction "2_2") (pintype "passive"))
      (node (ref "U$6") (pin "11") (pinfunction "A_11") (pintype "bidirectional"))
      (node (ref "U$8") (pin "A") (pinfunction "A_A") (pintype "bidirectional"))
    )
    (net (code "53") (name "Net-(U$6-B)") (class "Default")
      (node (ref "R8") (pin "2") (pinfunction "2_2") (pintype "passive"))
      (node (ref "U$6") (pin "12") (pinfunction "B_12") (pintype "bidirectional"))
      (node (ref "U$8") (pin "B") (pinfunction "B_B") (pintype "bidirectional"))
    )
    (net (code "54") (name "Net-(U$6-C)") (class "Default")
      (node (ref "R7") (pin "2") (pinfunction "2_2") (pintype "passive"))
      (node (ref "U$6") (pin "13") (pinfunction "C_13") (pintype "bidirectional"))
      (node (ref "U$9") (pin "A") (pinfunction "A_A") (pintype "bidirectional"))
    )
    (net (code "55") (name "Net-(U$6-D)") (class "Default")
      (node (ref "R5") (pin "2") (pinfunction "2_2") (pintype "passive"))
      (node (ref "U$6") (pin "14") (pinfunction "D_14") (pintype "bidirectional"))
      (node (ref "U$9") (pin "B") (pinfunction "B_B") (pintype "bidirectional"))
    )
    (net (code "56") (name "Net-(U$11-C1+)") (class "Default")
      (node (ref "C8") (pin "2") (pinfunction "2_2") (pintype "passive"))
      (node (ref "C9") (pin "2") (pinfunction "2_2") (pintype "passive"))
      (node (ref "U$11") (pin "18") (pinfunction "C1+_18") (pintype "bidirectional"))
    )
    (net (code "57") (name "Net-(U$11-C1-)") (class "Default")
      (node (ref "C9") (pin "1") (pinfunction "1_1") (pintype "passive"))
      (node (ref "U$11") (pin "17") (pinfunction "C1-_17") (pintype "bidirectional"))
    )
    (net (code "58") (name "Net-(U$11-C2+)") (class "Default")
      (node (ref "C10") (pin "1") (pinfunction "1_1") (pintype "passive"))
      (node (ref "U$11") (pin "19") (pinfunction "C2+_19") (pintype "bidirectional"))
    )
    (net (code "59") (name "Net-(U$11-C2-)") (class "Default")
      (node (ref "C10") (pin "2") (pinfunction "2_2") (pintype "passive"))
      (node (ref "U$11") (pin "20") (pinfunction "C2-_20") (pintype "bidirectional"))
    )
    (net (code "60") (name "Net-(U$11-C3-)") (class "Default")
      (node (ref "C8") (pin "1") (pinfunction "1_1") (pintype "passive"))
      (node (ref "U$11") (pin "16") (pinfunction "C3-_16") (pintype "bidirectional"))
    )
    (net (code "61") (name "Net-(U$11-V0)") (class "Default")
      (node (ref "C12") (pin "1") (pinfunction "1_1") (pintype "passive"))
      (node (ref "U$11") (pin "27") (pinfunction "V0_27") (pintype "bidirectional"))
    )
    (net (code "62") (name "Net-(U$11-V1)") (class "Default")
      (node (ref "C13") (pin "1") (pinfunction "1_1") (pintype "passive"))
      (node (ref "U$11") (pin "26") (pinfunction "V1_26") (pintype "bidirectional"))
    )
    (net (code "63") (name "Net-(U$11-V2)") (class "Default")
      (node (ref "C14") (pin "1") (pinfunction "1_1") (pintype "passive"))
      (node (ref "U$11") (pin "25") (pinfunction "V2_25") (pintype "bidirectional"))
    )
    (net (code "64") (name "Net-(U$11-V3)") (class "Default")
      (node (ref "C15") (pin "1") (pinfunction "1_1") (pintype "passive"))
      (node (ref "U$11") (pin "24") (pinfunction "V3_24") (pintype "bidirectional"))
    )
    (net (code "65") (name "Net-(U$11-V4)") (class "Default")
      (node (ref "C16") (pin "1") (pinfunction "1_1") (pintype "passive"))
      (node (ref "U$11") (pin "23") (pinfunction "V4_23") (pintype "bidirectional"))
    )
    (net (code "66") (name "Net-(U$11-VOUT)") (class "Default")
      (node (ref "C11") (pin "2") (pinfunction "2_2") (pintype "passive"))
      (node (ref "U$11") (pin "15") (pinfunction "VOUT_15") (pintype "bidirectional"))
    )
    (net (code "67") (name "Net-(U$15-CKIN)") (class "Default")
      (node (ref "C18") (pin "2") (pinfunction "2_2") (pintype "passive"))
      (node (ref "R18") (pin "1") (pinfunction "1_1") (pintype "passive"))
      (node (ref "U$15") (pin "8") (pinfunction "CKIN_8") (pintype "bidirectional"))
    )
    (net (code "68") (name "Net-(U$16-AUD_IN)") (class "Default")
      (node (ref "C22") (pin "1") (pinfunction "1_1") (pintype "passive"))
      (node (ref "TP2") (pin "TP") (pinfunction "TP_TP") (pintype "input"))
      (node (ref "U$16") (pin "2") (pinfunction "AUD_IN_2") (pintype "bidirectional"))
    )
    (net (code "69") (name "Net-(U$16-BYPASS)") (class "Default")
      (node (ref "C20") (pin "2") (pinfunction "2_2") (pintype "passive"))
      (node (ref "U$16") (pin "7") (pinfunction "BYPASS_7") (pintype "bidirectional"))
    )
    (net (code "70") (name "Net-(U$16-VOL)") (class "Default")
      (node (ref "C21") (pin "1") (pinfunction "1_1") (pintype "passive"))
      (node (ref "R23") (pin "2") (pinfunction "2_2") (pintype "passive"))
      (node (ref "TP1") (pin "TP") (pinfunction "TP_TP") (pintype "input"))
      (node (ref "U$16") (pin "4") (pinfunction "VOL_4") (pintype "bidirectional"))
    )
    (net (code "71") (name "unconnected-(SV1-Pad3)") (class "Default")
      (node (ref "SV1") (pin "3") (pinfunction "3_3") (pintype "passive"))
    )
    (net (code "72") (name "unconnected-(SV1-Pad4)") (class "Default")
      (node (ref "SV1") (pin "4") (pinfunction "4_4") (pintype "passive"))
    )
    (net (code "73") (name "unconnected-(SW0-Pad1)") (class "Default")
      (node (ref "SW0") (pin "1") (pintype "bidirectional"))
    )
    (net (code "74") (name "unconnected-(SW1-Pad1)") (class "Default")
      (node (ref "SW1") (pin "1") (pintype "bidirectional"))
    )
    (net (code "75") (name "unconnected-(SW2-Pad1)") (class "Default")
      (node (ref "SW2") (pin "1") (pintype "bidirectional"))
    )
    (net (code "76") (name "unconnected-(SW3-Pad1)") (class "Default")
      (node (ref "SW3") (pin "1") (pintype "bidirectional"))
    )
    (net (code "77") (name "unconnected-(U$1-PA2-Pad42)") (class "Default")
      (node (ref "U$1") (pin "42") (pinfunction "PA2_42") (pintype "bidirectional"))
    )
    (net (code "78") (name "unconnected-(U$1-PA3-Pad43)") (class "Default")
      (node (ref "U$1") (pin "43") (pinfunction "PA3_43") (pintype "bidirectional"))
    )
    (net (code "79") (name "unconnected-(U$1-PA4-Pad44)") (class "Default")
      (node (ref "U$1") (pin "44") (pinfunction "PA4_44") (pintype "bidirectional"))
    )
    (net (code "80") (name "unconnected-(U$1-PA5-Pad1)") (class "Default")
      (node (ref "U$1") (pin "1") (pinfunction "PA5_1") (pintype "bidirectional"))
    )
    (net (code "81") (name "unconnected-(U$1-PA6-Pad2)") (class "Default")
      (node (ref "U$1") (pin "2") (pinfunction "PA6_2") (pintype "bidirectional"))
    )
    (net (code "82") (name "unconnected-(U$1-PA7-Pad3)") (class "Default")
      (node (ref "U$1") (pin "3") (pinfunction "PA7_3") (pintype "bidirectional"))
    )
    (net (code "83") (name "unconnected-(U$1-PB1-Pad5)") (class "Default")
      (node (ref "U$1") (pin "5") (pinfunction "PB1_5") (pintype "bidirectional"))
    )
    (net (code "84") (name "unconnected-(U$1-PB3-Pad7)") (class "Default")
      (node (ref "U$1") (pin "7") (pinfunction "PB3_7") (pintype "bidirectional"))
    )
    (net (code "85") (name "unconnected-(U$1-PE1-Pad29)") (class "Default")
      (node (ref "U$1") (pin "29") (pinfunction "PE1_29") (pintype "bidirectional"))
    )
    (net (code "86") (name "unconnected-(U$1-PR0-Pad36)") (class "Default")
      (node (ref "U$1") (pin "36") (pinfunction "PR0_36") (pintype "bidirectional"))
    )
    (net (code "87") (name "unconnected-(U$1-PR1-Pad37)") (class "Default")
      (node (ref "U$1") (pin "37") (pinfunction "PR1_37") (pintype "bidirectional"))
    )
    (net (code "88") (name "unconnected-(U$6-~{QH}-Pad7)") (class "Default")
      (node (ref "U$6") (pin "7") (pinfunction "~{QH}_7") (pintype "bidirectional"))
    )
    (net (code "89") (name "unconnected-(U$7-Pad3)") (class "Default")
      (node (ref "U$7") (pin "3") (pintype "bidirectional"))
    )
    (net (code "90") (name "unconnected-(U$7-Pad4)") (class "Default")
      (node (ref "U$7") (pin "4") (pintype "bidirectional"))
    )
    (net (code "91") (name "unconnected-(U$10-CTS-Pad12)") (class "Default")
      (node (ref "U$10") (pin "12") (pinfunction "CTS_12") (pintype "output"))
    )
    (net (code "92") (name "unconnected-(U$10-DIO0-Pad20)") (class "Default")
      (node (ref "U$10") (pin "20") (pinfunction "DIO0_20") (pintype "bidirectional"))
    )
    (net (code "93") (name "unconnected-(U$10-DIO1-Pad19)") (class "Default")
      (node (ref "U$10") (pin "19") (pinfunction "DIO1_19") (pintype "bidirectional"))
    )
    (net (code "94") (name "unconnected-(U$10-DIO2-Pad18)") (class "Default")
      (node (ref "U$10") (pin "18") (pinfunction "DIO2_18") (pintype "bidirectional"))
    )
    (net (code "95") (name "unconnected-(U$10-DIO3-Pad17)") (class "Default")
      (node (ref "U$10") (pin "17") (pinfunction "DIO3_17") (pintype "bidirectional"))
    )
    (net (code "96") (name "unconnected-(U$10-DIO4-Pad11)") (class "Default")
      (node (ref "U$10") (pin "11") (pinfunction "DIO4_11") (pintype "bidirectional"))
    )
    (net (code "97") (name "unconnected-(U$10-DIO5-Pad15)") (class "Default")
      (node (ref "U$10") (pin "15") (pinfunction "DIO5_15") (pintype "bidirectional"))
    )
    (net (code "98") (name "unconnected-(U$10-DIO9-Pad13)") (class "Default")
      (node (ref "U$10") (pin "13") (pinfunction "DIO9_13") (pintype "bidirectional"))
    )
    (net (code "99") (name "unconnected-(U$10-DIO11-Pad7)") (class "Default")
      (node (ref "U$10") (pin "7") (pinfunction "DIO11_7") (pintype "bidirectional"))
    )
    (net (code "100") (name "unconnected-(U$10-DIO12-Pad4)") (class "Default")
      (node (ref "U$10") (pin "4") (pinfunction "DIO12_4") (pintype "bidirectional"))
    )
    (net (code "101") (name "unconnected-(U$10-DTR-Pad9)") (class "Default")
      (node (ref "U$10") (pin "9") (pinfunction "DTR_9") (pintype "bidirectional"))
    )
    (net (code "102") (name "unconnected-(U$10-RES-Pad8)") (class "Default")
      (node (ref "U$10") (pin "8") (pinfunction "RES_8") (pintype "bidirectional"))
    )
    (net (code "103") (name "unconnected-(U$10-RES-Pad14)") (class "Default")
      (node (ref "U$10") (pin "14") (pinfunction "RES_14") (pintype "bidirectional"))
    )
    (net (code "104") (name "unconnected-(U$10-RESET-Pad5)") (class "Default")
      (node (ref "U$10") (pin "5") (pinfunction "RESET_5") (pintype "input"))
    )
    (net (code "105") (name "unconnected-(U$10-RTS-Pad16)") (class "Default")
      (node (ref "U$10") (pin "16") (pinfunction "RTS_16") (pintype "input"))
    )
    (net (code "106") (name "unconnected-(U$11-D0-Pad6)") (class "Default")
      (node (ref "U$11") (pin "6") (pinfunction "D0_6") (pintype "bidirectional"))
    )
    (net (code "107") (name "unconnected-(U$11-D1-Pad7)") (class "Default")
      (node (ref "U$11") (pin "7") (pinfunction "D1_7") (pintype "bidirectional"))
    )
    (net (code "108") (name "unconnected-(U$11-D2-Pad8)") (class "Default")
      (node (ref "U$11") (pin "8") (pinfunction "D2_8") (pintype "bidirectional"))
    )
    (net (code "109") (name "unconnected-(U$11-D3-Pad9)") (class "Default")
      (node (ref "U$11") (pin "9") (pinfunction "D3_9") (pintype "bidirectional"))
    )
    (net (code "110") (name "unconnected-(U$11-D4-Pad10)") (class "Default")
      (node (ref "U$11") (pin "10") (pinfunction "D4_10") (pintype "bidirectional"))
    )
    (net (code "111") (name "unconnected-(U$11-D5-Pad11)") (class "Default")
      (node (ref "U$11") (pin "11") (pinfunction "D5_11") (pintype "bidirectional"))
    )
    (net (code "112") (name "unconnected-(U$11-VR-Pad28)") (class "Default")
      (node (ref "U$11") (pin "28") (pinfunction "VR_28") (pintype "bidirectional"))
    )
    (net (code "113") (name "unconnected-(U$14-Pad1)") (class "Default")
      (node (ref "U$14") (pin "1") (pintype "bidirectional"))
    )
    (net (code "114") (name "unconnected-(U$16-VOUT2-Pad8)") (class "Default")
      (node (ref "U$16") (pin "8") (pinfunction "VOUT2_8") (pintype "bidirectional"))
    )
  )
)
